# Sheet1.net
KiCad netlist of a schematic drawn in Altium Designer
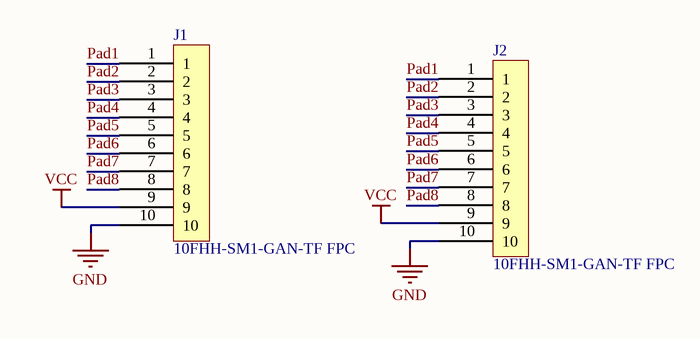
[diagram p0: Sheet1.SchDoc]

(export (version "E")
  (design (tool "Eeschema 10.0.6"))
  (components
    (comp (ref "J1")
      (value "10FHH-SM1-GAN-TF FPC")
      (footprint "PCBComponent_1")
      (libsource (lib "Rishabh_Schematic_Library") (part "10FHH-SM1-GAN-TF FPC"))
    )
    (comp (ref "J2")
      (value "10FHH-SM1-GAN-TF FPC")
      (footprint "PCBComponent_1")
      (libsource (lib "Rishabh_Schematic_Library") (part "10FHH-SM1-GAN-TF FPC"))
    )
  )
  (nets
    (net (code "1") (name "/Pad1") (class "Default")
      (node (ref "J1") (pin "1") (pinfunction "1_1") (pintype "passive"))
      (node (ref "J2") (pin "1") (pinfunction "1_1") (pintype "passive"))
    )
    (net (code "2") (name "/Pad2") (class "Default")
      (node (ref "J1") (pin "2") (pinfunction "2_2") (pintype "passive"))
      (node (ref "J2") (pin "2") (pinfunction "2_2") (pintype "passive"))
    )
    (net (code "3") (name "/Pad3") (class "Default")
      (node (ref "J1") (pin "3") (pinfunction "3_3") (pintype "passive"))
      (node (ref "J2") (pin "3") (pinfunction "3_3") (pintype "passive"))
    )
    (net (code "4") (name "/Pad4") (class "Default")
      (node (ref "J1") (pin "4") (pinfunction "4_4") (pintype "passive"))
      (node (ref "J2") (pin "4") (pinfunction "4_4") (pintype "passive"))
    )
    (net (code "5") (name "/Pad5") (class "Default")
      (node (ref "J1") (pin "5") (pinfunction "5_5") (pintype "passive"))
      (node (ref "J2") (pin "5") (pinfunction "5_5") (pintype "passive"))
    )
    (net (code "6") (name "/Pad6") (class "Default")
      (node (ref "J1") (pin "6") (pinfunction "6_6") (pintype "passive"))
      (node (ref "J2") (pin "6") (pinfunction "6_6") (pintype "passive"))
    )
    (net (code "7") (name "/Pad7") (class "Default")
      (node (ref "J1") (pin "7") (pinfunction "7_7") (pintype "passive"))
      (node (ref "J2") (pin "7") (pinfunction "7_7") (pintype "passive"))
    )
    (net (code "8") (name "/Pad8") (class "Default")
      (node (ref "J1") (pin "8") (pinfunction "8_8") (pintype "passive"))
      (node (ref "J2") (pin "8") (pinfunction "8_8") (pintype "passive"))
    )
    (net (code "9") (name "GND") (class "Default")
      (node (ref "J1") (pin "10") (pinfunction "10_10") (pintype "passive"))
      (node (ref "J2") (pin "10") (pinfunction "10_10") (pintype "passive"))
    )
    (net (code "10") (name "VCC") (class "Default")
      (node (ref "J1") (pin "9") (pinfunction "9_9") (pintype "passive"))
      (node (ref "J2") (pin "9") (pinfunction "9_9") (pintype "passive"))
    )
  )
)
